# POWER.net
KiCad netlist of a schematic drawn in Altium Designer
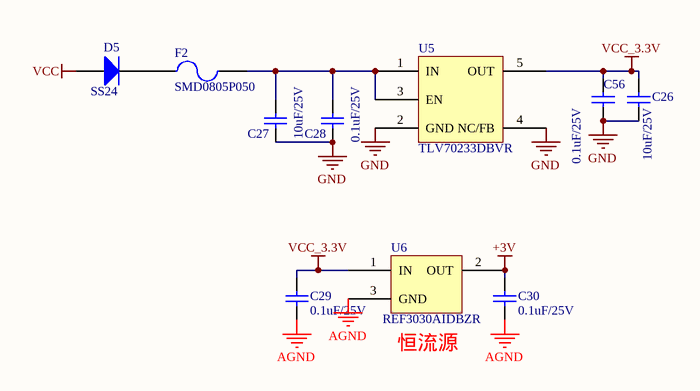
[diagram p0: POWER.SchDoc]

(export (version "E")
  (design (tool "Eeschema 10.0.6"))
  (components
    (comp (ref "C26")
      (value "10uF/25V")
      (footprint "0603C")
      (description "Capacitor")
      (fields (field (name "PUBLISHER") "Altium Limited"))
      (libsource (lib "Miscellaneous Devices") (part "Cap"))
    )
    (comp (ref "C27")
      (value "10uF/25V")
      (footprint "0603C")
      (description "Capacitor")
      (fields (field (name "PUBLISHER") "Altium Limited"))
      (libsource (lib "Miscellaneous Devices") (part "Cap"))
    )
    (comp (ref "C28")
      (value "0.1uF/25V")
      (footprint "0603C")
      (description "Capacitor")
      (fields (field (name "PUBLISHER") "Altium Limited"))
      (libsource (lib "Miscellaneous Devices") (part "Cap"))
    )
    (comp (ref "C29")
      (value "0.1uF/25V")
      (footprint "0603C")
      (description "Capacitor")
      (fields (field (name "PUBLISHER") "Altium Limited"))
      (libsource (lib "Miscellaneous Devices") (part "Cap"))
    )
    (comp (ref "C30")
      (value "0.1uF/25V")
      (footprint "0603C")
      (description "Capacitor")
      (fields (field (name "PUBLISHER") "Altium Limited"))
      (libsource (lib "Miscellaneous Devices") (part "Cap"))
    )
    (comp (ref "C56")
      (value "0.1uF/25V")
      (footprint "0603C")
      (description "Capacitor")
      (fields (field (name "PUBLISHER") "Altium Limited"))
      (libsource (lib "Miscellaneous Devices") (part "Cap"))
    )
    (comp (ref "D5")
      (value "SS24")
      (footprint "SMA")
      (description "High Conductance Fast Diode")
      (fields (field (name "PUBLISHER") "Altium Limited"))
      (libsource (lib "Miscellaneous Devices") (part "Diode 1N4148"))
    )
    (comp (ref "F2")
      (value "SMD0805P050")
      (footprint "0805R")
      (description "Fuse")
      (fields (field (name "PUBLISHER") "Altium Limited"))
      (libsource (lib "Miscellaneous Devices") (part "Fuse 2"))
    )
    (comp (ref "U5")
      (value "TLV70233DBVR")
      (footprint "SOT23-5(DBV)")
      (libsource (lib "Schlib_20110825") (part "TLV70230DBVR"))
    )
    (comp (ref "U6")
      (value "REF3030AIDBZR")
      (footprint "SOT23-3")
      (libsource (lib "Schlib1") (part "REF3012"))
    )
  )
  (nets
    (net (code "1") (name "+3V") (class "Default")
      (node (ref "C30") (pin "1") (pinfunction "1_1") (pintype "passive"))
      (node (ref "U6") (pin "2") (pinfunction "OUT_2") (pintype "passive"))
    )
    (net (code "2") (name "AGND") (class "Default")
      (node (ref "C29") (pin "2") (pinfunction "2_2") (pintype "passive"))
      (node (ref "C30") (pin "2") (pinfunction "2_2") (pintype "passive"))
      (node (ref "U6") (pin "3") (pinfunction "GND_3") (pintype "passive"))
    )
    (net (code "3") (name "GND") (class "Default")
      (node (ref "C26") (pin "1") (pinfunction "1_1") (pintype "passive"))
      (node (ref "C27") (pin "1") (pinfunction "1_1") (pintype "passive"))
      (node (ref "C28") (pin "2") (pinfunction "2_2") (pintype "passive"))
      (node (ref "C56") (pin "2") (pinfunction "2_2") (pintype "passive"))
      (node (ref "U5") (pin "2") (pinfunction "GND_2") (pintype "passive"))
      (node (ref "U5") (pin "4") (pinfunction "NC/FB_4") (pintype "passive"))
    )
    (net (code "4") (name "Net-(D5-K)") (class "Default")
      (node (ref "D5") (pin "2") (pinfunction "K_2") (pintype "passive"))
      (node (ref "F2") (pin "1") (pinfunction "1_1") (pintype "passive"))
    )
    (net (code "5") (name "Net-(U5-EN)") (class "Default")
      (node (ref "C27") (pin "2") (pinfunction "2_2") (pintype "passive"))
      (node (ref "C28") (pin "1") (pinfunction "1_1") (pintype "passive"))
      (node (ref "F2") (pin "2") (pinfunction "2_2") (pintype "passive"))
      (node (ref "U5") (pin "1") (pinfunction "IN_1") (pintype "passive"))
      (node (ref "U5") (pin "3") (pinfunction "EN_3") (pintype "passive"))
    )
    (net (code "6") (name "VCC") (class "Default")
      (node (ref "D5") (pin "1") (pinfunction "A_1") (pintype "passive"))
    )
    (net (code "7") (name "VCC_3.3V") (class "Default")
      (node (ref "C26") (pin "2") (pinfunction "2_2") (pintype "passive"))
      (node (ref "C29") (pin "1") (pinfunction "1_1") (pintype "passive"))
      (node (ref "C56") (pin "1") (pinfunction "1_1") (pintype "passive"))
      (node (ref "U5") (pin "5") (pinfunction "OUT_5") (pintype "passive"))
      (node (ref "U6") (pin "1") (pinfunction "IN_1") (pintype "passive"))
    )
  )
)
